# Power_typec.net
KiCad netlist of a schematic drawn in Altium Designer
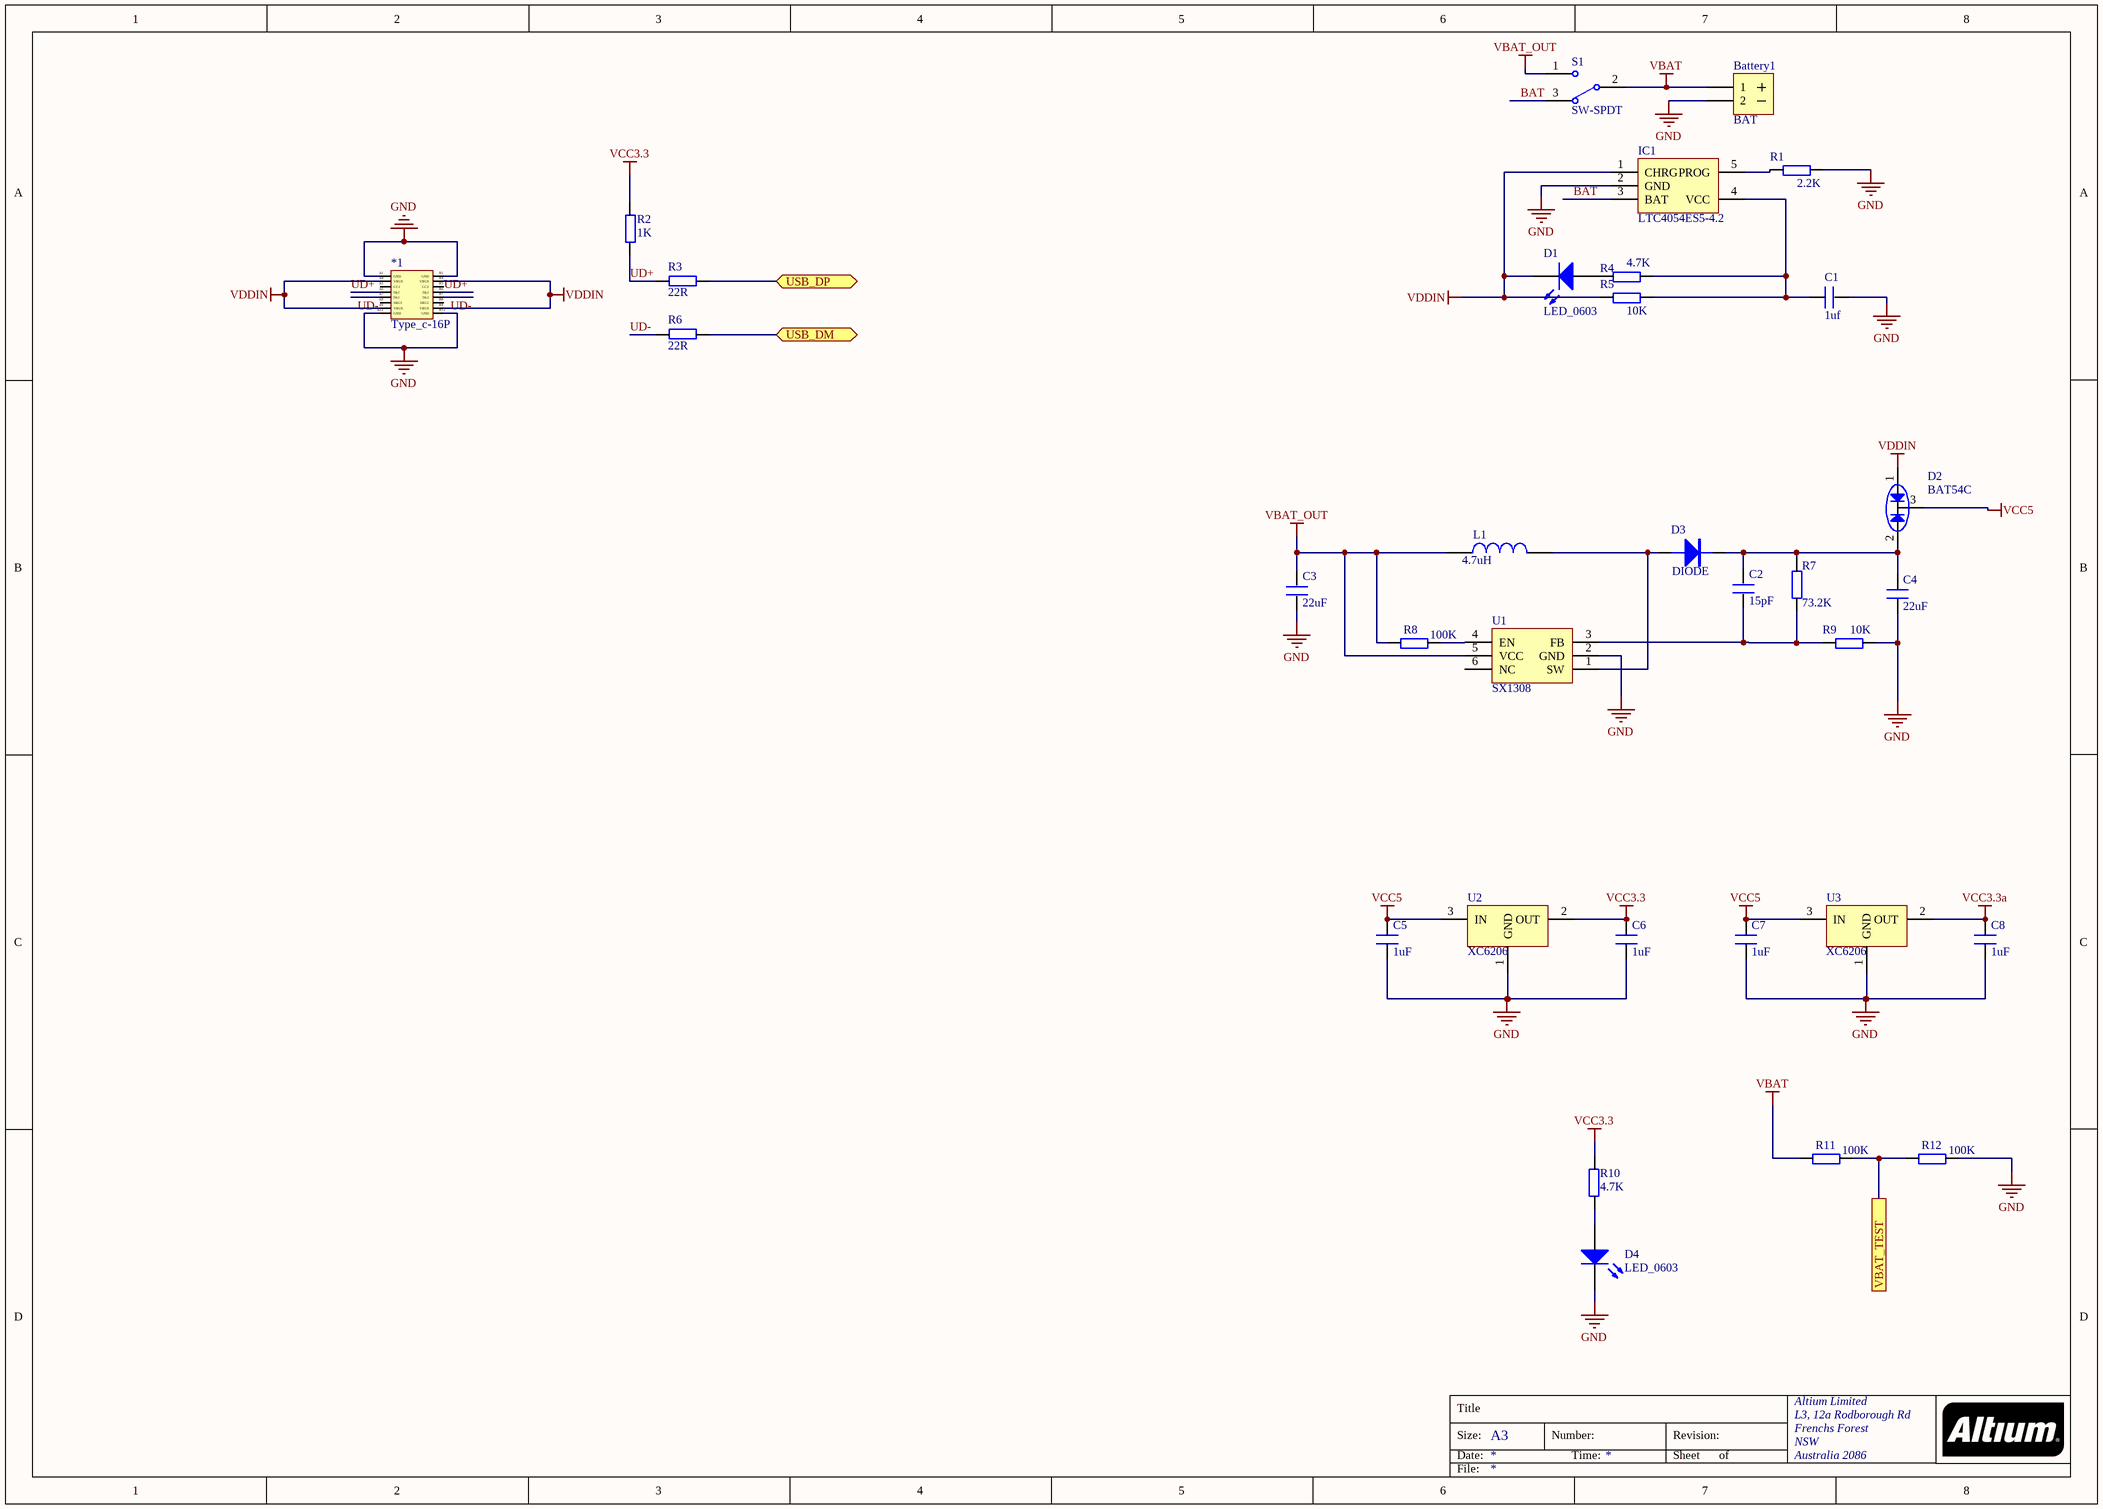
[diagram p0: Power&typec.SchDoc]

(export (version "E")
  (design (tool "Eeschema 10.0.6"))
  (components
    (comp (ref "*1")
      (value "Type_c-16P")
      (footprint "TYPE-C-16P")
      (libsource (lib "USB&typeC") (part "Type_c-16P"))
    )
    (comp (ref "Battery1")
      (value "BAT")
      (footprint "BAT")
      (description "Header, 2-Pin")
      (fields (field (name "PUBLISHER") "mazhongwei"))
      (libsource (lib "RoboFly") (part "BAT"))
    )
    (comp (ref "C1") (value "1uf") (footprint "0603P") (libsource (lib "Explorer STM32F407封装库") (part "C")))
    (comp (ref "C2") (value "15pF") (footprint "0603P") (libsource (lib "Explorer STM32F407封装库") (part "C")))
    (comp (ref "C3") (value "22uF") (footprint "0603P") (libsource (lib "Explorer STM32F407封装库") (part "C")))
    (comp (ref "C4") (value "22uF") (footprint "0603P") (libsource (lib "Explorer STM32F407封装库") (part "C")))
    (comp (ref "C5") (value "1uF") (footprint "0603P") (libsource (lib "Explorer STM32F407封装库") (part "C")))
    (comp (ref "C6") (value "1uF") (footprint "0603P") (libsource (lib "Explorer STM32F407封装库") (part "C")))
    (comp (ref "C7") (value "1uF") (footprint "0603P") (libsource (lib "Explorer STM32F407封装库") (part "C")))
    (comp (ref "C8") (value "1uF") (footprint "0603P") (libsource (lib "Explorer STM32F407封装库") (part "C")))
    (comp (ref "D1")
      (value "LED_0603")
      (footprint "LED-0603")
      (description "发光二极管")
      (fields (field (name "PUBLISHER") "Altium Limited"))
      (libsource (lib "RoboFly") (part "LED 0603"))
    )
    (comp (ref "D2")
      (value "BAT54C")
      (footprint "SOT23-3M")
      (description "表贴肖特基二极管")
      (fields (field (name "版权归属") "源创客"))
      (libsource (lib "RoboFly") (part "BAT54C"))
    )
    (comp (ref "D3")
      (value "DIODE")
      (footprint "SMA/DO-214AC")
      (description "普通二极管")
      (libsource (lib "二极管") (part "DIODE"))
    )
    (comp (ref "D4")
      (value "LED_0603")
      (footprint "LED-0603")
      (description "发光二极管")
      (fields (field (name "PUBLISHER") "Altium Limited"))
      (libsource (lib "RoboFly") (part "LED 0603"))
    )
    (comp (ref "IC1")
      (value "LTC4054ES5-4.2")
      (footprint "SOT23-5M")
      (description "锂电池充电芯片")
      (fields (field (name "版权归属") "源创客"))
      (libsource (lib "RoboFly") (part "LTC4054"))
    )
    (comp (ref "L1")
      (value "INDUCTOR")
      (footprint "AL0204")
      (fields (field (name "ALTIUM_UNNAMED_1") "4.7uH"))
      (libsource (lib "电感") (part "INDUCTOR"))
    )
    (comp (ref "R1") (value "2.2K") (footprint "0603P") (libsource (lib "Explorer STM32F407封装库") (part "R")))
    (comp (ref "R2") (value "1K") (footprint "0603P") (libsource (lib "Explorer STM32F407封装库") (part "R")))
    (comp (ref "R3") (value "22R") (footprint "0603P") (libsource (lib "Explorer STM32F407封装库") (part "R")))
    (comp (ref "R4") (value "4.7K") (footprint "0603P") (libsource (lib "Explorer STM32F407封装库") (part "R")))
    (comp (ref "R5") (value "10K") (footprint "0603P") (libsource (lib "Explorer STM32F407封装库") (part "R")))
    (comp (ref "R6") (value "22R") (footprint "0603P") (libsource (lib "Explorer STM32F407封装库") (part "R")))
    (comp (ref "R7") (value "73.2K") (footprint "0603P") (libsource (lib "Explorer STM32F407封装库") (part "R")))
    (comp (ref "R8") (value "100K") (footprint "0603P") (libsource (lib "Explorer STM32F407封装库") (part "R")))
    (comp (ref "R9") (value "10K") (footprint "0603P") (libsource (lib "Explorer STM32F407封装库") (part "R")))
    (comp (ref "R10") (value "4.7K") (footprint "0603P") (libsource (lib "Explorer STM32F407封装库") (part "R")))
    (comp (ref "R11") (value "100K") (footprint "0603P") (libsource (lib "Explorer STM32F407封装库") (part "R")))
    (comp (ref "R12") (value "100K") (footprint "0603P") (libsource (lib "Explorer STM32F407封装库") (part "R")))
    (comp (ref "S1")
      (value "SW-SPDT")
      (footprint "SWITCH_PWR")
      (description "SPDT Subminiature Toggle Switch, Right Angle Mounting, Vertical Actuation")
      (fields (field (name "PUBLISHER") "mazhongwei"))
      (libsource (lib "RoboFly") (part "SW-SPDT"))
    )
    (comp (ref "U1")
      (value "SX1308")
      (footprint "SOT23-6")
      (description "可调升压芯片")
      (libsource (lib "电源芯片") (part "SX1308"))
    )
    (comp (ref "U2")
      (value "XC6206")
      (footprint "RoboFly:SOT23-3M")
      (fields (field (name "PUBLISHER") "mazhongwei"))
      (libsource (lib "RoboFly") (part "XC6206"))
    )
    (comp (ref "U3")
      (value "XC6206")
      (footprint "RoboFly:SOT23-3M")
      (fields (field (name "PUBLISHER") "mazhongwei"))
      (libsource (lib "RoboFly") (part "XC6206"))
    )
  )
  (nets
    (net (code "1") (name "/BAT") (class "Default")
      (node (ref "IC1") (pin "3") (pinfunction "BAT_3") (pintype "passive"))
      (node (ref "S1") (pin "3") (pinfunction "3_3") (pintype "passive"))
    )
    (net (code "2") (name "/UD+") (class "Default")
      (node (ref "*1") (pin "A6") (pinfunction "Dp1_A6") (pintype "passive"))
      (node (ref "*1") (pin "B6") (pinfunction "Dp2_B6") (pintype "passive"))
      (node (ref "R2") (pin "1") (pintype "passive"))
      (node (ref "R3") (pin "2") (pintype "passive"))
    )
    (net (code "3") (name "/UD-") (class "Default")
      (node (ref "*1") (pin "A7") (pinfunction "Dn1_A7") (pintype "passive"))
      (node (ref "*1") (pin "B7") (pinfunction "Dn2_B7") (pintype "passive"))
      (node (ref "R6") (pin "2") (pintype "passive"))
    )
    (net (code "4") (name "/USB_DM") (class "Default") (node (ref "R6") (pin "1") (pintype "passive")))
    (net (code "5") (name "/USB_DP") (class "Default") (node (ref "R3") (pin "1") (pintype "passive")))
    (net (code "6") (name "/VBAT_TEST") (class "Default")
      (node (ref "R11") (pin "2") (pintype "passive"))
      (node (ref "R12") (pin "1") (pintype "passive"))
    )
    (net (code "7") (name "GND") (class "Default")
      (node (ref "*1") (pin "A1") (pinfunction "GND_A1") (pintype "passive"))
      (node (ref "*1") (pin "A12") (pinfunction "GND_A12") (pintype "passive"))
      (node (ref "*1") (pin "B1") (pinfunction "GND_B1") (pintype "passive"))
      (node (ref "*1") (pin "B12") (pinfunction "GND_B12") (pintype "passive"))
      (node (ref "Battery1") (pin "2") (pinfunction "2_2") (pintype "passive"))
      (node (ref "C1") (pin "2") (pintype "passive"))
      (node (ref "C3") (pin "2") (pintype "passive"))
      (node (ref "C4") (pin "2") (pintype "passive"))
      (node (ref "C5") (pin "2") (pintype "passive"))
      (node (ref "C6") (pin "2") (pintype "passive"))
      (node (ref "C7") (pin "2") (pintype "passive"))
      (node (ref "C8") (pin "2") (pintype "passive"))
      (node (ref "D4") (pin "2") (pinfunction "2_2") (pintype "passive"))
      (node (ref "IC1") (pin "2") (pinfunction "GND_2") (pintype "passive"))
      (node (ref "R1") (pin "2") (pintype "passive"))
      (node (ref "R12") (pin "2") (pintype "passive"))
      (node (ref "R9") (pin "2") (pintype "passive"))
      (node (ref "U1") (pin "2") (pinfunction "GND_2") (pintype "passive"))
      (node (ref "U2") (pin "1") (pinfunction "GND_1") (pintype "passive"))
      (node (ref "U3") (pin "1") (pinfunction "GND_1") (pintype "passive"))
    )
    (net (code "8") (name "Net-(C2-Pad1)") (class "Default")
      (node (ref "C2") (pin "1") (pintype "passive"))
      (node (ref "C4") (pin "1") (pintype "passive"))
      (node (ref "D2") (pin "2") (pinfunction "2_2") (pintype "passive"))
      (node (ref "D3") (pin "K") (pinfunction "K_K") (pintype "passive"))
      (node (ref "R7") (pin "2") (pintype "passive"))
    )
    (net (code "9") (name "Net-(D1-Pad1)") (class "Default")
      (node (ref "D1") (pin "1") (pinfunction "1_1") (pintype "passive"))
      (node (ref "R4") (pin "1") (pintype "passive"))
    )
    (net (code "10") (name "Net-(D4-Pad1)") (class "Default")
      (node (ref "D4") (pin "1") (pinfunction "1_1") (pintype "passive"))
      (node (ref "R10") (pin "2") (pintype "passive"))
    )
    (net (code "11") (name "Net-(IC1-PROG)") (class "Default")
      (node (ref "IC1") (pin "5") (pinfunction "PROG_5") (pintype "passive"))
      (node (ref "R1") (pin "1") (pintype "passive"))
    )
    (net (code "12") (name "Net-(IC1-VCC)") (class "Default")
      (node (ref "C1") (pin "1") (pintype "passive"))
      (node (ref "IC1") (pin "4") (pinfunction "VCC_4") (pintype "passive"))
      (node (ref "R4") (pin "2") (pintype "passive"))
      (node (ref "R5") (pin "2") (pintype "passive"))
    )
    (net (code "13") (name "Net-(U1-EN)") (class "Default")
      (node (ref "R8") (pin "2") (pintype "passive"))
      (node (ref "U1") (pin "4") (pinfunction "EN_4") (pintype "passive"))
    )
    (net (code "14") (name "Net-(U1-FB)") (class "Default")
      (node (ref "C2") (pin "2") (pintype "passive"))
      (node (ref "R7") (pin "1") (pintype "passive"))
      (node (ref "R9") (pin "1") (pintype "passive"))
      (node (ref "U1") (pin "3") (pinfunction "FB_3") (pintype "passive"))
    )
    (net (code "15") (name "Net-(U1-SW)") (class "Default")
      (node (ref "D3") (pin "A") (pinfunction "A_A") (pintype "passive"))
      (node (ref "L1") (pin "2") (pinfunction "2_2") (pintype "passive"))
      (node (ref "U1") (pin "1") (pinfunction "SW_1") (pintype "passive"))
    )
    (net (code "16") (name "VBAT") (class "Default")
      (node (ref "Battery1") (pin "1") (pinfunction "1_1") (pintype "passive"))
      (node (ref "R11") (pin "1") (pintype "passive"))
      (node (ref "S1") (pin "2") (pinfunction "2_2") (pintype "passive"))
    )
    (net (code "17") (name "VBAT_OUT") (class "Default")
      (node (ref "C3") (pin "1") (pintype "passive"))
      (node (ref "L1") (pin "1") (pinfunction "1_1") (pintype "passive"))
      (node (ref "R8") (pin "1") (pintype "passive"))
      (node (ref "S1") (pin "1") (pinfunction "1_1") (pintype "passive"))
      (node (ref "U1") (pin "5") (pinfunction "VCC_5") (pintype "passive"))
    )
    (net (code "18") (name "VCC3.3") (class "Default")
      (node (ref "C6") (pin "1") (pintype "passive"))
      (node (ref "R10") (pin "1") (pintype "passive"))
      (node (ref "R2") (pin "2") (pintype "passive"))
      (node (ref "U2") (pin "2") (pinfunction "OUT_2") (pintype "passive"))
    )
    (net (code "19") (name "VCC3.3a") (class "Default")
      (node (ref "C8") (pin "1") (pintype "passive"))
      (node (ref "U3") (pin "2") (pinfunction "OUT_2") (pintype "passive"))
    )
    (net (code "20") (name "VCC5") (class "Default")
      (node (ref "C5") (pin "1") (pintype "passive"))
      (node (ref "C7") (pin "1") (pintype "passive"))
      (node (ref "D2") (pin "3") (pinfunction "3_3") (pintype "passive"))
      (node (ref "U2") (pin "3") (pinfunction "IN_3") (pintype "passive"))
      (node (ref "U3") (pin "3") (pinfunction "IN_3") (pintype "passive"))
    )
    (net (code "21") (name "VDDIN") (class "Default")
      (node (ref "*1") (pin "A4") (pinfunction "VBUS_A4") (pintype "passive"))
      (node (ref "*1") (pin "A9") (pinfunction "VBUS_A9") (pintype "passive"))
      (node (ref "*1") (pin "B4") (pinfunction "VBUS_B4") (pintype "passive"))
      (node (ref "*1") (pin "B9") (pinfunction "VBUS_B9") (pintype "passive"))
      (node (ref "D1") (pin "2") (pinfunction "2_2") (pintype "passive"))
      (node (ref "D2") (pin "1") (pinfunction "1_1") (pintype "passive"))
      (node (ref "IC1") (pin "1") (pinfunction "CHRG_1") (pintype "passive"))
      (node (ref "R5") (pin "1") (pintype "passive"))
    )
    (net (code "22") (name "unconnected-(*1-CC1-PadA5)") (class "Default")
      (node (ref "*1") (pin "A5") (pinfunction "CC1_A5") (pintype "passive"))
    )
    (net (code "23") (name "unconnected-(*1-CC2-PadB5)") (class "Default")
      (node (ref "*1") (pin "B5") (pinfunction "CC2_B5") (pintype "passive"))
    )
    (net (code "24") (name "unconnected-(*1-SBU1-PadA8)") (class "Default")
      (node (ref "*1") (pin "A8") (pinfunction "SBU1_A8") (pintype "passive"))
    )
    (net (code "25") (name "unconnected-(*1-SBU2-PadB8)") (class "Default")
      (node (ref "*1") (pin "B8") (pinfunction "SBU2_B8") (pintype "passive"))
    )
    (net (code "26") (name "unconnected-(U1-NC-Pad6)") (class "Default")
      (node (ref "U1") (pin "6") (pinfunction "NC_6") (pintype "passive"))
    )
  )
)
